# bat-phone_Dodo.net
KiCad netlist of a schematic drawn in EAGLE
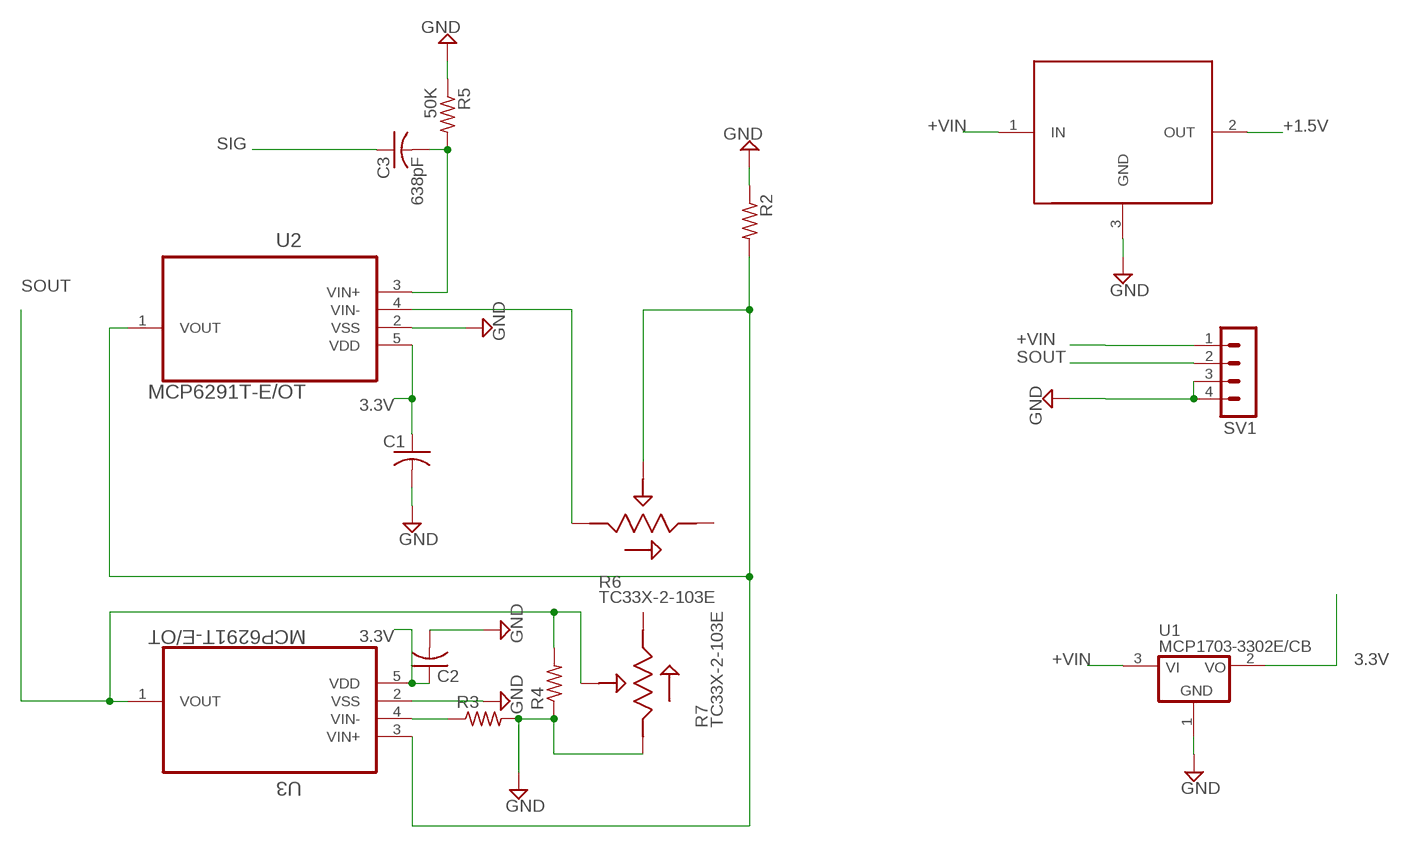
[diagram p0: schematic, sheet 1]

(export (version "E")
  (design (tool "Eeschema 10.0.6"))
  (components
    (comp (ref "C1")
      (value "C-USC0603K")
      (footprint "eagle-import:C0603K")
      (libsource (lib "eagle-import") (part "C-USC0603K"))
    )
    (comp (ref "C2")
      (value "C-USC0603K")
      (footprint "eagle-import:C0603K")
      (libsource (lib "eagle-import") (part "C-USC0603K"))
    )
    (comp (ref "C3")
      (value "638pF")
      (footprint "eagle-import:C0603K")
      (libsource (lib "eagle-import") (part "C-USC0603K"))
    )
    (comp (ref "R2")
      (value "R-US_R0603")
      (footprint "eagle-import:R0603")
      (libsource (lib "eagle-import") (part "R-US_R0603"))
    )
    (comp (ref "R3")
      (value "R-US_R0603")
      (footprint "eagle-import:R0603")
      (libsource (lib "eagle-import") (part "R-US_R0603"))
    )
    (comp (ref "R4")
      (value "R-US_R0603")
      (footprint "eagle-import:R0603")
      (libsource (lib "eagle-import") (part "R-US_R0603"))
    )
    (comp (ref "R5")
      (value "50K")
      (footprint "eagle-import:R0603")
      (libsource (lib "eagle-import") (part "R-US_R0603"))
    )
    (comp (ref "R6")
      (value "TC33X-2-103E")
      (footprint "eagle-import:35WR")
      (fields (field (name "MF") "Bourns"))
      (libsource (lib "eagle-import") (part "TC33X-2-103E"))
    )
    (comp (ref "R7")
      (value "TC33X-2-103E")
      (footprint "eagle-import:35WR")
      (fields (field (name "MF") "Bourns"))
      (libsource (lib "eagle-import") (part "TC33X-2-103E"))
    )
    (comp (ref "SV1")
      (value "MA04-1")
      (footprint "eagle-import:MA04-1")
      (libsource (lib "eagle-import") (part "MA04-1"))
    )
    (comp (ref "U$1")
      (value "AP7313")
      (footprint "eagle-import:SOT23-R")
      (libsource (lib "eagle-import") (part "AP7313"))
    )
    (comp (ref "U1")
      (value "MCP1703-3302E/CB")
      (footprint "eagle-import:SOT23A_MICROCHIP_CB")
      (libsource (lib "eagle-import") (part "MCP170302E/CB-33"))
    )
    (comp (ref "U2")
      (value "MCP6291T-E/OT")
      (footprint "eagle-import:SOT95P320X145-5N")
      (fields (field (name "MF") "Microchip"))
      (libsource (lib "eagle-import") (part "MCP6291T-E/OT"))
    )
    (comp (ref "U3")
      (value "MCP6291T-E/OT")
      (footprint "eagle-import:SOT95P320X145-5N")
      (fields (field (name "MF") "Microchip"))
      (libsource (lib "eagle-import") (part "MCP6291T-E/OT"))
    )
  )
  (nets
    (net (code "1") (name "/+1.5V") (class "Default")
      (node (ref "U$1") (pin "2") (pinfunction "OUT_2") (pintype "bidirectional"))
    )
    (net (code "2") (name "/+VIN") (class "Default")
      (node (ref "SV1") (pin "1") (pinfunction "1_1") (pintype "passive"))
      (node (ref "U$1") (pin "1") (pinfunction "IN_1") (pintype "bidirectional"))
      (node (ref "U1") (pin "3") (pinfunction "VI_3") (pintype "power_in"))
    )
    (net (code "3") (name "/3.3V") (class "Default")
      (node (ref "C1") (pin "1") (pinfunction "1_1") (pintype "passive"))
      (node (ref "C2") (pin "1") (pinfunction "1_1") (pintype "passive"))
      (node (ref "U1") (pin "2") (pinfunction "VO_2") (pintype "passive"))
      (node (ref "U2") (pin "5") (pinfunction "VDD_5") (pintype "power_in"))
      (node (ref "U3") (pin "5") (pinfunction "VDD_5") (pintype "power_in"))
    )
    (net (code "4") (name "/SIG") (class "Default")
      (node (ref "C3") (pin "1") (pinfunction "1_1") (pintype "passive"))
    )
    (net (code "5") (name "/SOUT") (class "Default")
      (node (ref "R4") (pin "2") (pinfunction "2_2") (pintype "passive"))
      (node (ref "R7") (pin "2") (pinfunction "2_2") (pintype "passive"))
      (node (ref "SV1") (pin "2") (pinfunction "2_2") (pintype "passive"))
      (node (ref "U3") (pin "1") (pinfunction "VOUT_1") (pintype "output"))
    )
    (net (code "6") (name "GND") (class "Default")
      (node (ref "C1") (pin "2") (pinfunction "2_2") (pintype "passive"))
      (node (ref "C2") (pin "2") (pinfunction "2_2") (pintype "passive"))
      (node (ref "R2") (pin "1") (pinfunction "1_1") (pintype "passive"))
      (node (ref "R3") (pin "2") (pinfunction "2_2") (pintype "passive"))
      (node (ref "R4") (pin "1") (pinfunction "1_1") (pintype "passive"))
      (node (ref "R5") (pin "1") (pinfunction "1_1") (pintype "passive"))
      (node (ref "R7") (pin "1") (pinfunction "1_1") (pintype "passive"))
      (node (ref "SV1") (pin "3") (pinfunction "3_3") (pintype "passive"))
      (node (ref "SV1") (pin "4") (pinfunction "4_4") (pintype "passive"))
      (node (ref "U$1") (pin "3") (pinfunction "GND_3") (pintype "bidirectional"))
      (node (ref "U1") (pin "1") (pinfunction "GND_1") (pintype "power_in"))
      (node (ref "U2") (pin "2") (pinfunction "VSS_2") (pintype "passive"))
      (node (ref "U3") (pin "2") (pinfunction "VSS_2") (pintype "passive"))
    )
    (net (code "7") (name "Net-(U2-VIN+)") (class "Default")
      (node (ref "C3") (pin "2") (pinfunction "2_2") (pintype "passive"))
      (node (ref "R5") (pin "2") (pinfunction "2_2") (pintype "passive"))
      (node (ref "U2") (pin "3") (pinfunction "VIN+_3") (pintype "input"))
    )
    (net (code "8") (name "Net-(U2-VIN-)") (class "Default")
      (node (ref "R6") (pin "1") (pinfunction "1_1") (pintype "passive"))
      (node (ref "U2") (pin "4") (pinfunction "VIN-_4") (pintype "input"))
    )
    (net (code "9") (name "Net-(U2-VOUT)") (class "Default")
      (node (ref "R2") (pin "2") (pinfunction "2_2") (pintype "passive"))
      (node (ref "R6") (pin "2") (pinfunction "2_2") (pintype "passive"))
      (node (ref "U2") (pin "1") (pinfunction "VOUT_1") (pintype "output"))
      (node (ref "U3") (pin "3") (pinfunction "VIN+_3") (pintype "input"))
    )
    (net (code "10") (name "Net-(U3-VIN-)") (class "Default")
      (node (ref "R3") (pin "1") (pinfunction "1_1") (pintype "passive"))
      (node (ref "U3") (pin "4") (pinfunction "VIN-_4") (pintype "input"))
    )
    (net (code "11") (name "unconnected-(R6-Pad3)") (class "Default")
      (node (ref "R6") (pin "3") (pinfunction "3_3") (pintype "passive"))
    )
    (net (code "12") (name "unconnected-(R7-Pad3)") (class "Default")
      (node (ref "R7") (pin "3") (pinfunction "3_3") (pintype "passive"))
    )
  )
)
